# QEP.net
KiCad netlist of a schematic drawn in Altium Designer
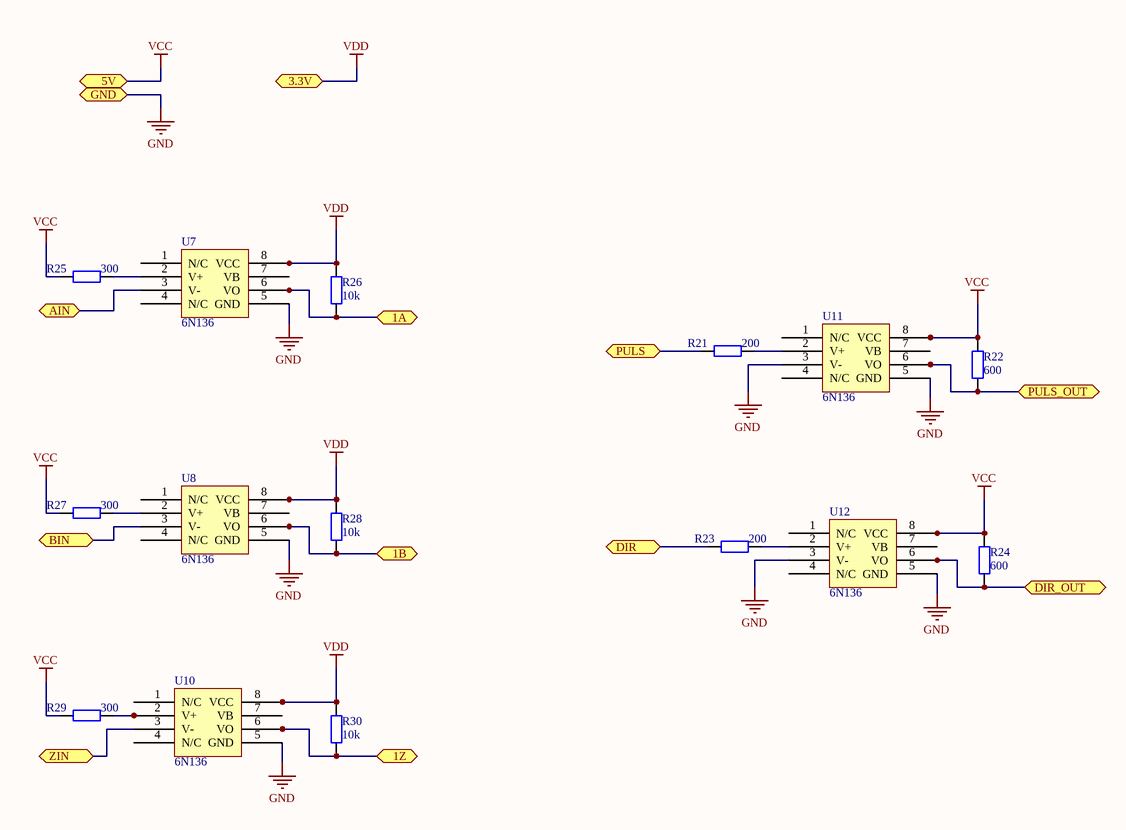
[diagram p0: QEP.SchDoc]

(export (version "E")
  (design (tool "Eeschema 10.0.6"))
  (components
    (comp (ref "R21")
      (value "200")
      (footprint "0805")
      (fields (field (name "Comment") "RES"))
      (libsource (lib "Schlib1") (part "RES"))
    )
    (comp (ref "R22")
      (value "600")
      (footprint "0805")
      (fields (field (name "Comment") "RES"))
      (libsource (lib "") (part "RES_1"))
    )
    (comp (ref "R23")
      (value "200")
      (footprint "0805")
      (fields (field (name "Comment") "RES"))
      (libsource (lib "Schlib1") (part "RES"))
    )
    (comp (ref "R24")
      (value "600")
      (footprint "0805")
      (fields (field (name "Comment") "RES"))
      (libsource (lib "") (part "RES_1"))
    )
    (comp (ref "R25")
      (value "300")
      (footprint "0805")
      (fields (field (name "Comment") "RES"))
      (libsource (lib "Schlib1") (part "RES"))
    )
    (comp (ref "R26")
      (value "10k")
      (footprint "0805")
      (fields (field (name "Comment") "RES"))
      (libsource (lib "") (part "RES_1"))
    )
    (comp (ref "R27")
      (value "300")
      (footprint "0805")
      (fields (field (name "Comment") "RES"))
      (libsource (lib "Schlib1") (part "RES"))
    )
    (comp (ref "R28")
      (value "10k")
      (footprint "0805")
      (fields (field (name "Comment") "RES"))
      (libsource (lib "") (part "RES_1"))
    )
    (comp (ref "R29")
      (value "300")
      (footprint "0805")
      (fields (field (name "Comment") "RES"))
      (libsource (lib "Schlib1") (part "RES"))
    )
    (comp (ref "R30")
      (value "10k")
      (footprint "0805")
      (fields (field (name "Comment") "RES"))
      (libsource (lib "") (part "RES_1"))
    )
    (comp (ref "U7") (value "6N136") (footprint "SOP8") (libsource (lib "6N136") (part "Component_1")))
    (comp (ref "U8") (value "6N136") (footprint "SOP8") (libsource (lib "6N136") (part "Component_1")))
    (comp (ref "U10") (value "6N136") (footprint "SOP8") (libsource (lib "6N136") (part "Component_1")))
    (comp (ref "U11") (value "6N136") (footprint "SOP8") (libsource (lib "6N136") (part "Component_1")))
    (comp (ref "U12") (value "6N136") (footprint "SOP8") (libsource (lib "6N136") (part "Component_1")))
  )
  (nets
    (net (code "1") (name "/1A") (class "Default")
      (node (ref "R26") (pin "1") (pintype "passive"))
      (node (ref "U7") (pin "6") (pinfunction "VO_6") (pintype "passive"))
    )
    (net (code "2") (name "/1B") (class "Default")
      (node (ref "R28") (pin "1") (pintype "passive"))
      (node (ref "U8") (pin "6") (pinfunction "VO_6") (pintype "passive"))
    )
    (net (code "3") (name "/1Z") (class "Default")
      (node (ref "R30") (pin "1") (pintype "passive"))
      (node (ref "U10") (pin "6") (pinfunction "VO_6") (pintype "passive"))
    )
    (net (code "4") (name "/AIN") (class "Default")
      (node (ref "U7") (pin "3") (pinfunction "V-_3") (pintype "passive"))
    )
    (net (code "5") (name "/BIN") (class "Default")
      (node (ref "U8") (pin "3") (pinfunction "V-_3") (pintype "passive"))
    )
    (net (code "6") (name "/DIR") (class "Default") (node (ref "R23") (pin "1") (pintype "passive")))
    (net (code "7") (name "/DIR_OUT") (class "Default")
      (node (ref "R24") (pin "1") (pintype "passive"))
      (node (ref "U12") (pin "6") (pinfunction "VO_6") (pintype "passive"))
    )
    (net (code "8") (name "/PULS") (class "Default") (node (ref "R21") (pin "1") (pintype "passive")))
    (net (code "9") (name "/PULS_OUT") (class "Default")
      (node (ref "R22") (pin "1") (pintype "passive"))
      (node (ref "U11") (pin "6") (pinfunction "VO_6") (pintype "passive"))
    )
    (net (code "10") (name "/ZIN") (class "Default")
      (node (ref "U10") (pin "3") (pinfunction "V-_3") (pintype "passive"))
    )
    (net (code "11") (name "GND") (class "Default")
      (node (ref "U10") (pin "5") (pinfunction "GND_5") (pintype "passive"))
      (node (ref "U11") (pin "3") (pinfunction "V-_3") (pintype "passive"))
      (node (ref "U11") (pin "5") (pinfunction "GND_5") (pintype "passive"))
      (node (ref "U12") (pin "3") (pinfunction "V-_3") (pintype "passive"))
      (node (ref "U12") (pin "5") (pinfunction "GND_5") (pintype "passive"))
      (node (ref "U7") (pin "5") (pinfunction "GND_5") (pintype "passive"))
      (node (ref "U8") (pin "5") (pinfunction "GND_5") (pintype "passive"))
    )
    (net (code "12") (name "Net-(U7-V+)") (class "Default")
      (node (ref "R25") (pin "2") (pintype "passive"))
      (node (ref "U7") (pin "2") (pinfunction "V+_2") (pintype "passive"))
    )
    (net (code "13") (name "Net-(U8-V+)") (class "Default")
      (node (ref "R27") (pin "2") (pintype "passive"))
      (node (ref "U8") (pin "2") (pinfunction "V+_2") (pintype "passive"))
    )
    (net (code "14") (name "Net-(U10-V+)") (class "Default")
      (node (ref "R29") (pin "2") (pintype "passive"))
      (node (ref "U10") (pin "2") (pinfunction "V+_2") (pintype "passive"))
    )
    (net (code "15") (name "Net-(U11-V+)") (class "Default")
      (node (ref "R21") (pin "2") (pintype "passive"))
      (node (ref "U11") (pin "2") (pinfunction "V+_2") (pintype "passive"))
    )
    (net (code "16") (name "Net-(U12-V+)") (class "Default")
      (node (ref "R23") (pin "2") (pintype "passive"))
      (node (ref "U12") (pin "2") (pinfunction "V+_2") (pintype "passive"))
    )
    (net (code "17") (name "VCC") (class "Default")
      (node (ref "R22") (pin "2") (pintype "passive"))
      (node (ref "R24") (pin "2") (pintype "passive"))
      (node (ref "R25") (pin "1") (pintype "passive"))
      (node (ref "R27") (pin "1") (pintype "passive"))
      (node (ref "R29") (pin "1") (pintype "passive"))
      (node (ref "U11") (pin "8") (pinfunction "VCC_8") (pintype "passive"))
      (node (ref "U12") (pin "8") (pinfunction "VCC_8") (pintype "passive"))
    )
    (net (code "18") (name "VDD") (class "Default")
      (node (ref "R26") (pin "2") (pintype "passive"))
      (node (ref "R28") (pin "2") (pintype "passive"))
      (node (ref "R30") (pin "2") (pintype "passive"))
      (node (ref "U10") (pin "8") (pinfunction "VCC_8") (pintype "passive"))
      (node (ref "U7") (pin "8") (pinfunction "VCC_8") (pintype "passive"))
      (node (ref "U8") (pin "8") (pinfunction "VCC_8") (pintype "passive"))
    )
    (net (code "19") (name "unconnected-(U7-N{slash}C-Pad1)") (class "Default")
      (node (ref "U7") (pin "1") (pinfunction "N/C_1") (pintype "passive"))
    )
    (net (code "20") (name "unconnected-(U7-N{slash}C-Pad4)") (class "Default")
      (node (ref "U7") (pin "4") (pinfunction "N/C_4") (pintype "passive"))
    )
    (net (code "21") (name "unconnected-(U7-VB-Pad7)") (class "Default")
      (node (ref "U7") (pin "7") (pinfunction "VB_7") (pintype "passive"))
    )
    (net (code "22") (name "unconnected-(U8-N{slash}C-Pad1)") (class "Default")
      (node (ref "U8") (pin "1") (pinfunction "N/C_1") (pintype "passive"))
    )
    (net (code "23") (name "unconnected-(U8-N{slash}C-Pad4)") (class "Default")
      (node (ref "U8") (pin "4") (pinfunction "N/C_4") (pintype "passive"))
    )
    (net (code "24") (name "unconnected-(U8-VB-Pad7)") (class "Default")
      (node (ref "U8") (pin "7") (pinfunction "VB_7") (pintype "passive"))
    )
    (net (code "25") (name "unconnected-(U10-N{slash}C-Pad1)") (class "Default")
      (node (ref "U10") (pin "1") (pinfunction "N/C_1") (pintype "passive"))
    )
    (net (code "26") (name "unconnected-(U10-N{slash}C-Pad4)") (class "Default")
      (node (ref "U10") (pin "4") (pinfunction "N/C_4") (pintype "passive"))
    )
    (net (code "27") (name "unconnected-(U10-VB-Pad7)") (class "Default")
      (node (ref "U10") (pin "7") (pinfunction "VB_7") (pintype "passive"))
    )
    (net (code "28") (name "unconnected-(U11-N{slash}C-Pad1)") (class "Default")
      (node (ref "U11") (pin "1") (pinfunction "N/C_1") (pintype "passive"))
    )
    (net (code "29") (name "unconnected-(U11-N{slash}C-Pad4)") (class "Default")
      (node (ref "U11") (pin "4") (pinfunction "N/C_4") (pintype "passive"))
    )
    (net (code "30") (name "unconnected-(U11-VB-Pad7)") (class "Default")
      (node (ref "U11") (pin "7") (pinfunction "VB_7") (pintype "passive"))
    )
    (net (code "31") (name "unconnected-(U12-N{slash}C-Pad1)") (class "Default")
      (node (ref "U12") (pin "1") (pinfunction "N/C_1") (pintype "passive"))
    )
    (net (code "32") (name "unconnected-(U12-N{slash}C-Pad4)") (class "Default")
      (node (ref "U12") (pin "4") (pinfunction "N/C_4") (pintype "passive"))
    )
    (net (code "33") (name "unconnected-(U12-VB-Pad7)") (class "Default")
      (node (ref "U12") (pin "7") (pinfunction "VB_7") (pintype "passive"))
    )
  )
)
